# Photocoupler12Vinput.net
KiCad netlist of a schematic drawn in Altium Designer
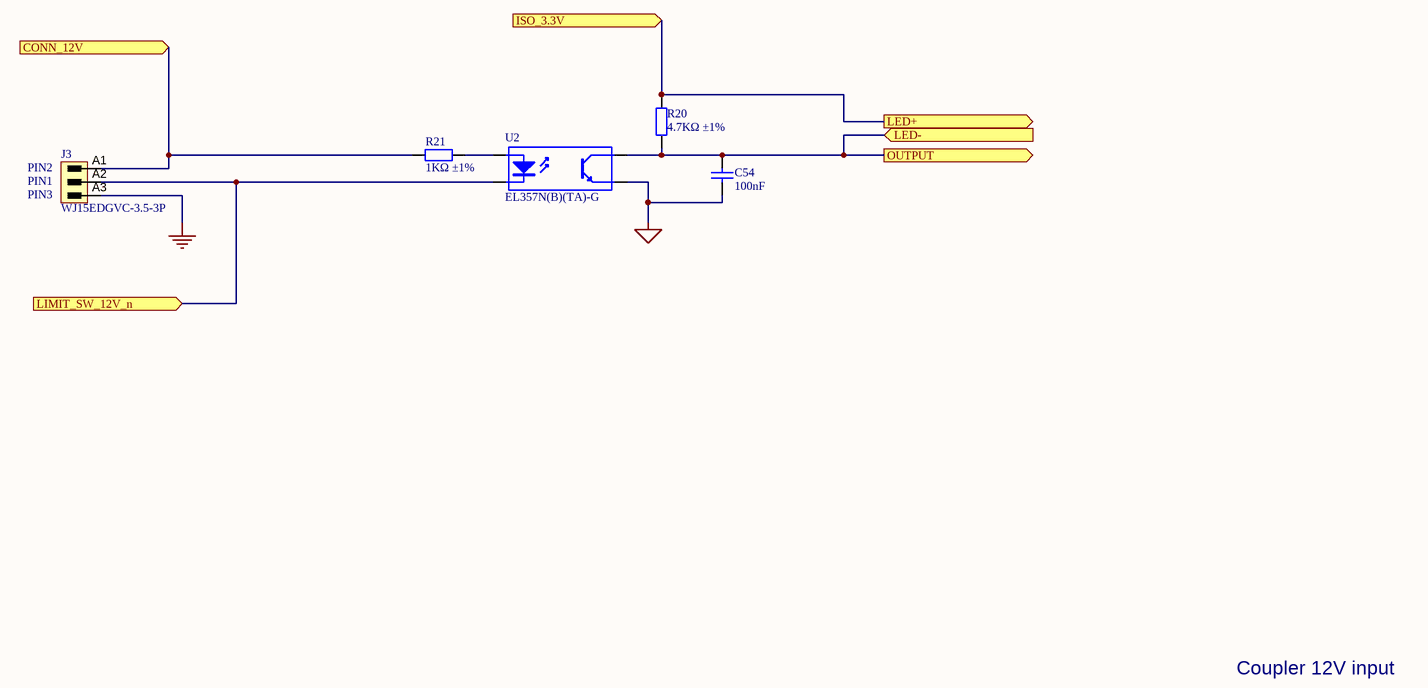
[diagram p0: Photocoupler12Vinput.SchDoc]

(export (version "E")
  (design (tool "Eeschema 10.0.6"))
  (components
    (comp (ref "C54")
      (value "100nF")
      (footprint "0603_C")
      (description "Chip capacitors")
      (fields (field (name "MANUFACTURER") "YAGEO") (field (name "PARTNUMBER") "CC0603KRX7R9BB104"))
      (libsource (lib "Cap") (part "0603 100nF (104) 10% 50V"))
    )
    (comp (ref "J3")
      (value "WJ15EDGVC-3.5-3P")
      (footprint "691321100003 - 3.5mm  3p")
      (fields (field (name "MANUFACTURER") "Ningbo Kangnex Elec"))
      (libsource (lib "Universal_CNC_Breakout") (part "3.5mm Terminal Header 3p"))
    )
    (comp (ref "R20")
      (value "4.7KΩ ±1%")
      (footprint "0603_R")
      (description "Chip resistor")
      (fields (field (name "MANUFACTURER") "Uniroyal Elec") (field (name "PARTNUMBER") "0603WAF4701T5E"))
      (libsource (lib "RES") (part "0603 4.7K (4701) 1%"))
    )
    (comp (ref "R21")
      (value "1KΩ ±1%")
      (footprint "0603_R")
      (description "Chip resistor")
      (fields (field (name "MANUFACTURER") "Uniroyal Elec") (field (name "PARTNUMBER") "0603WAF1001T5E"))
      (libsource (lib "RES") (part "0603 1K (1001) 1%"))
    )
    (comp (ref "U2")
      (value "EL357N(B)(TA)-G")
      (footprint "Miscellaneous Devices LC:SOP-4_P2.54")
      (description "OPTOISOLATOR 3.75KV TRANS 4-SOP")
      (libsource (lib "IC") (part "EL357N(B)(TA)-G_[C6649]"))
    )
  )
  (nets
    (net (code "1") (name "/CONN_12V") (class "Default")
      (node (ref "J3") (pin "A1") (pinfunction "A1_A1") (pintype "passive"))
      (node (ref "R21") (pin "1") (pinfunction "1_1") (pintype "passive"))
    )
    (net (code "2") (name "/ISO_3.3V") (class "Default")
      (node (ref "R20") (pin "2") (pinfunction "2_2") (pintype "passive"))
    )
    (net (code "3") (name "/LED-") (class "Default")
      (node (ref "C54") (pin "2") (pinfunction "2_2") (pintype "passive"))
      (node (ref "R20") (pin "1") (pinfunction "1_1") (pintype "passive"))
      (node (ref "U2") (pin "4") (pinfunction "C_4") (pintype "passive"))
    )
    (net (code "4") (name "/LIMIT_SW_12V_n") (class "Default")
      (node (ref "J3") (pin "A2") (pinfunction "A2_A2") (pintype "passive"))
      (node (ref "U2") (pin "2") (pinfunction "K_2") (pintype "passive"))
    )
    (net (code "5") (name "GND") (class "Default")
      (node (ref "J3") (pin "A3") (pinfunction "A3_A3") (pintype "passive"))
    )
    (net (code "6") (name "MCU_GND") (class "Default")
      (node (ref "C54") (pin "1") (pinfunction "1_1") (pintype "passive"))
      (node (ref "U2") (pin "3") (pinfunction "E_3") (pintype "passive"))
    )
    (net (code "7") (name "Net-(U2-A)") (class "Default")
      (node (ref "R21") (pin "2") (pinfunction "2_2") (pintype "passive"))
      (node (ref "U2") (pin "1") (pinfunction "A_1") (pintype "passive"))
    )
  )
)
